# Shot-Clock-Remote.net
KiCad netlist of a schematic drawn in Altium Designer
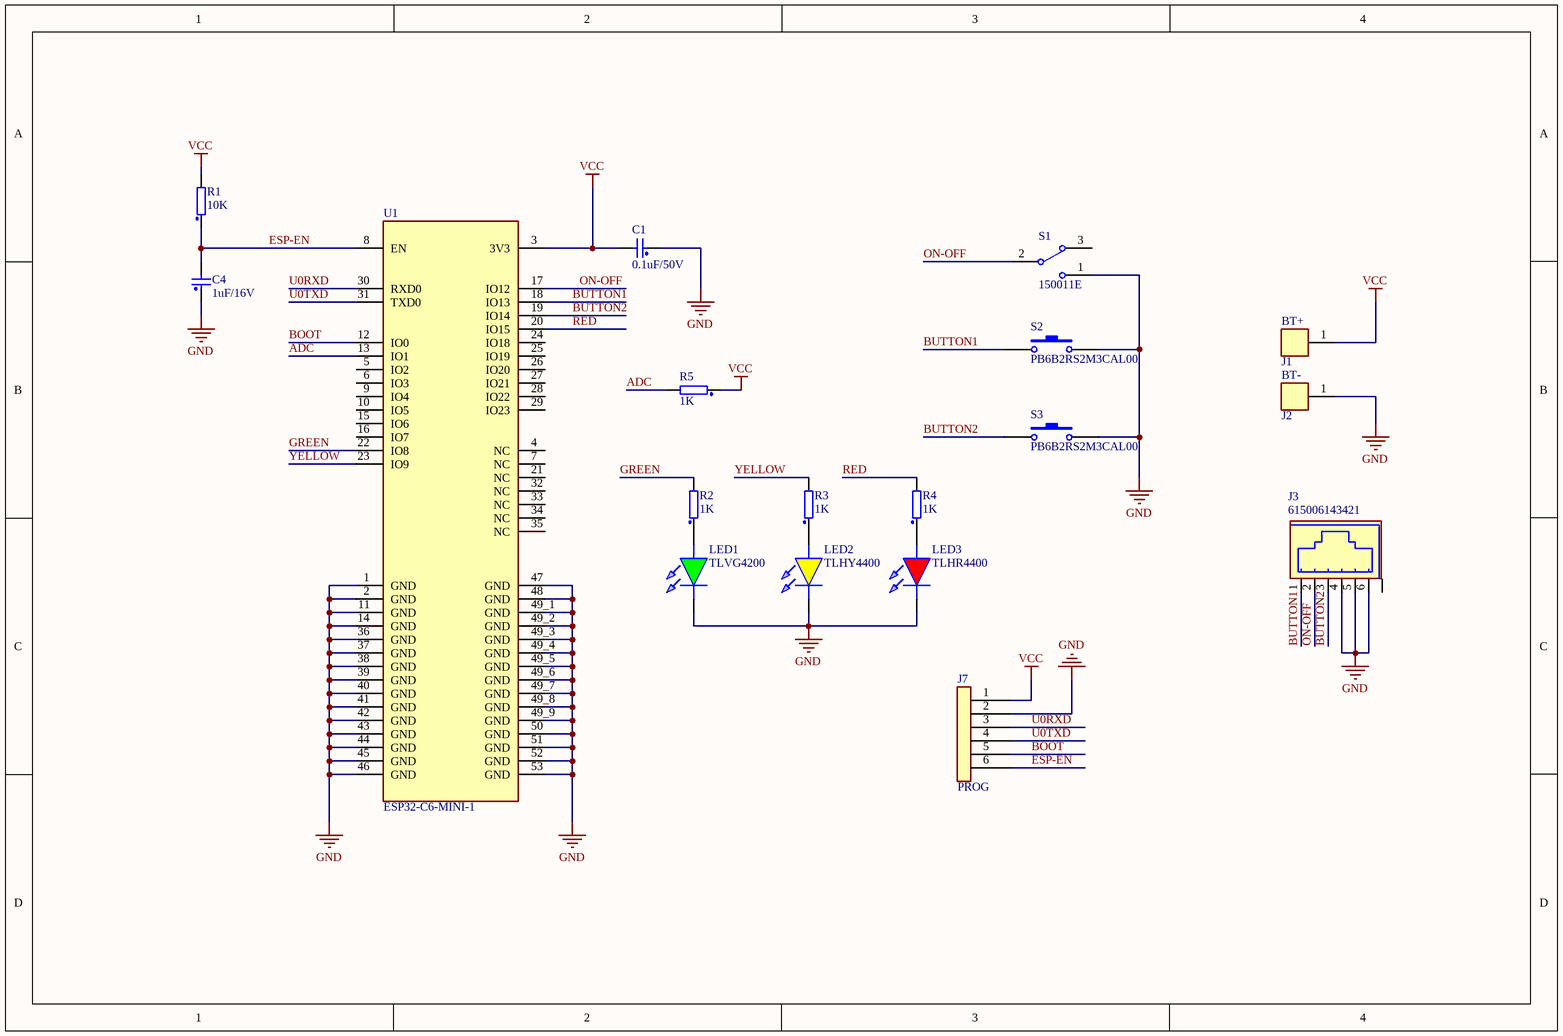
[diagram p0: Shot-Clock-Remote.SchDoc]

(export (version "E")
  (design (tool "Eeschema 10.0.6"))
  (components
    (comp (ref "C1")
      (value "0.1uF/50V")
      (footprint "CAP-0603")
      (description "Multilayer Ceramic Capacitors MLCC - SMD/SMT 50V 100nF X7R 0603 10%")
      (fields
        (field (name "MANUFACTURER") "YAGEO")
        (field (name "MANUFACTURER PART NUMBER") "CS0603KRX7R9BB104")
      )
      (libsource (lib "Dropbox") (part "CAP"))
    )
    (comp (ref "C4")
      (value "1uF/16V")
      (footprint "CAP-0603")
      (description "1 µF ±10% 25V Ceramic Capacitor X5R 0603 (1608 Metric)")
      (fields
        (field (name "MANUFACTURER") "YAGEO")
        (field (name "MANUFACTURER PART NUMBER") "CC0603KRX7R7BB105")
      )
      (libsource (lib "Dropbox") (part "CAP"))
    )
    (comp (ref "J1")
      (value "BT+")
      (footprint "BT_PAD")
      (description "NO FIT")
      (libsource (lib "ESP-Button") (part "BK-82"))
    )
    (comp (ref "J2")
      (value "BT-")
      (footprint "BT_PAD")
      (description "NO FIT")
      (libsource (lib "ESP-Button") (part "BK-82"))
    )
    (comp (ref "J3")
      (value "615006143421")
      (footprint "615006143421")
      (description "Modular Connectors / Ethernet Connectors WR-COM Modular Jack Horztl 1.5A")
      (fields (field (name "MANUFACTURER") "Wurth Elektronik"))
      (libsource (lib "615006143421") (part "615006143421"))
    )
    (comp (ref "J7")
      (value "PROG")
      (footprint "HEADER1X6")
      (description "Connector Header Through Hole 6 position 0.100\" (2.54mm)")
      (fields
        (field (name "MANUFACTURER") "Würth Elektronik")
        (field (name "MANUFACTURER PART NUMBER") "61300611121")
      )
      (libsource (lib "SCJ library") (part "HEADER6_1"))
    )
    (comp (ref "LED1")
      (value "TLVG4200")
      (footprint "LED3MM_GREEN")
      (description "Green 569nm LED Indication - Discrete 2.4V Radial")
      (fields (field (name "MANUFACTURER") "Vishay Semiconductor Opto Division"))
      (libsource (lib "ShotClockRemote") (part "LED GREEN DIP 3mm"))
    )
    (comp (ref "LED2")
      (value "TLHY4400")
      (footprint "LED3MM_YELLOW")
      (description "Yellow 588nm LED Indication - Discrete 2.4V Radial")
      (fields (field (name "MANUFACTURER") "Vishay Semiconductor Opto Division"))
      (libsource (lib "ShotClockRemote") (part "LED YELLOW DIP 3mm"))
    )
    (comp (ref "LED3")
      (value "TLHR4400")
      (footprint "LED3MM_RED")
      (description "Red 619nm LED Indication - Discrete 2V Radial")
      (fields (field (name "MANUFACTURER") "Vishay Semiconductor Opto Division"))
      (libsource (lib "ShotClockRemote") (part "LED RED DIP 3mm"))
    )
    (comp (ref "R1")
      (value "10K")
      (footprint "RES-0603")
      (description "10 kOhms ±1% 0.1W, 1/10W Chip Resistor 0603 (1608 Metric) Moisture Resistant Thick Film")
      (fields
        (field (name "MANUFACTURER PART NUMBER") "RC0603FR-0710KL")
        (field (name "MANUFACTURER") "YAGEO")
      )
      (libsource (lib "ShotClockRemote") (part "RES"))
    )
    (comp (ref "R2")
      (value "1K")
      (footprint "RES-0603")
      (description "1 KOhms ±1% 0.1W, 1/10W Chip Resistor 0603 (1608 Metric) Moisture Resistant Thick Film")
      (fields
        (field (name "MANUFACTURER PART NUMBER") "RC0603FR-071KL")
        (field (name "MANUFACTURER") "YAGEO")
      )
      (libsource (lib "ShotClockRemote") (part "RES1"))
    )
    (comp (ref "R3")
      (value "1K")
      (footprint "RES-0603")
      (description "1 KOhms ±1% 0.1W, 1/10W Chip Resistor 0603 (1608 Metric) Moisture Resistant Thick Film")
      (fields
        (field (name "MANUFACTURER PART NUMBER") "RC0603FR-071KL")
        (field (name "MANUFACTURER") "YAGEO")
      )
      (libsource (lib "ShotClockRemote") (part "RES1"))
    )
    (comp (ref "R4")
      (value "1K")
      (footprint "RES-0603")
      (description "1 KOhms ±1% 0.1W, 1/10W Chip Resistor 0603 (1608 Metric) Moisture Resistant Thick Film")
      (fields
        (field (name "MANUFACTURER PART NUMBER") "RC0603FR-071KL")
        (field (name "MANUFACTURER") "YAGEO")
      )
      (libsource (lib "ShotClockRemote") (part "RES1"))
    )
    (comp (ref "R5")
      (value "1K")
      (footprint "RES-0603")
      (description "1 KOhms ±1% 0.1W, 1/10W Chip Resistor 0603 (1608 Metric) Moisture Resistant Thick Film")
      (fields
        (field (name "MANUFACTURER PART NUMBER") "RC0603FR-071KL")
        (field (name "MANUFACTURER") "YAGEO")
      )
      (libsource (lib "ShotClockRemote") (part "RES1"))
    )
    (comp (ref "S1")
      (value "150011E")
      (footprint "150011E")
      (description "SPDT Subminiature Toggle Switch, Right Angle Mounting, Vertical Actuation")
      (fields (field (name "MANUFACTURER") "EATON"))
      (libsource (lib "Miscellaneous Devices") (part "SW-SPDT"))
    )
    (comp (ref "S2")
      (value "PB6B2RS2M3CAL00")
      (footprint "PB6B2RS2M3CAL00")
      (description "Pushbutton Switch SPST-NO Standard Panel Mount, Front")
      (fields (field (name "MANUFACTURER") "TE Connectivity ALCOSWITCH Switches"))
      (libsource (lib "ShotClockRemote") (part "SW-PB"))
    )
    (comp (ref "S3")
      (value "PB6B2RS2M3CAL00")
      (footprint "PB6B2RS2M3CAL00")
      (description "Pushbutton Switch SPST-NO Standard Panel Mount, Front")
      (fields (field (name "MANUFACTURER") "TE Connectivity ALCOSWITCH Switches"))
      (libsource (lib "ShotClockRemote") (part "SW-PB"))
    )
    (comp (ref "U1")
      (value "ESP32-C6-MINI-1")
      (footprint "XCVR_ESP32-C6-MINI-1")
      (fields
        (field (name "MANUFACTURER PART NUMBER") "ESP32-C3-MINI-1-N4")
        (field (name "MANUFACTURER") "Espressif Systems")
      )
      (libsource (lib "ESP-Button") (part "ESP32-C6-MINI-1"))
    )
  )
  (nets
    (net (code "1") (name "/ADC") (class "Default")
      (node (ref "R5") (pin "2") (pintype "passive"))
      (node (ref "U1") (pin "13") (pinfunction "IO1_13") (pintype "passive"))
    )
    (net (code "2") (name "/BOOT") (class "Default")
      (node (ref "J7") (pin "5") (pintype "passive"))
      (node (ref "U1") (pin "12") (pinfunction "IO0_12") (pintype "passive"))
    )
    (net (code "3") (name "/BUTTON1") (class "Default")
      (node (ref "J3") (pin "1") (pinfunction "6_1") (pintype "passive"))
      (node (ref "S2") (pin "1") (pinfunction "1_1") (pintype "passive"))
      (node (ref "U1") (pin "18") (pinfunction "IO13_18") (pintype "passive"))
    )
    (net (code "4") (name "/BUTTON2") (class "Default")
      (node (ref "J3") (pin "3") (pinfunction "4_3") (pintype "passive"))
      (node (ref "S3") (pin "1") (pinfunction "1_1") (pintype "passive"))
      (node (ref "U1") (pin "19") (pinfunction "IO14_19") (pintype "passive"))
    )
    (net (code "5") (name "/ESP-EN") (class "Default")
      (node (ref "C4") (pin "2") (pinfunction "2_2") (pintype "passive"))
      (node (ref "J7") (pin "6") (pintype "passive"))
      (node (ref "R1") (pin "1") (pintype "passive"))
      (node (ref "U1") (pin "8") (pinfunction "EN_8") (pintype "passive"))
    )
    (net (code "6") (name "/GREEN") (class "Default")
      (node (ref "R2") (pin "2") (pintype "passive"))
      (node (ref "U1") (pin "22") (pinfunction "IO8_22") (pintype "passive"))
    )
    (net (code "7") (name "/ON-OFF") (class "Default")
      (node (ref "J3") (pin "2") (pinfunction "5_2") (pintype "passive"))
      (node (ref "S1") (pin "2") (pinfunction "2_2") (pintype "passive"))
      (node (ref "U1") (pin "17") (pinfunction "IO12_17") (pintype "passive"))
    )
    (net (code "8") (name "/RED") (class "Default")
      (node (ref "R4") (pin "2") (pintype "passive"))
      (node (ref "U1") (pin "20") (pinfunction "IO15_20") (pintype "passive"))
    )
    (net (code "9") (name "/U0RXD") (class "Default")
      (node (ref "J7") (pin "3") (pintype "passive"))
      (node (ref "U1") (pin "30") (pinfunction "RXD0_30") (pintype "passive"))
    )
    (net (code "10") (name "/U0TXD") (class "Default")
      (node (ref "J7") (pin "4") (pintype "passive"))
      (node (ref "U1") (pin "31") (pinfunction "TXD0_31") (pintype "passive"))
    )
    (net (code "11") (name "/YELLOW") (class "Default")
      (node (ref "R3") (pin "2") (pintype "passive"))
      (node (ref "U1") (pin "23") (pinfunction "IO9_23") (pintype "passive"))
    )
    (net (code "12") (name "GND") (class "Default")
      (node (ref "C1") (pin "1") (pinfunction "1_1") (pintype "passive"))
      (node (ref "C4") (pin "1") (pinfunction "1_1") (pintype "passive"))
      (node (ref "J2") (pin "1") (pinfunction "1_1") (pintype "passive"))
      (node (ref "J3") (pin "4") (pinfunction "3_4") (pintype "passive"))
      (node (ref "J3") (pin "5") (pinfunction "2_5") (pintype "passive"))
      (node (ref "J3") (pin "6") (pinfunction "1_6") (pintype "passive"))
      (node (ref "J7") (pin "2") (pintype "passive"))
      (node (ref "LED1") (pin "K") (pinfunction "K_K") (pintype "passive"))
      (node (ref "LED2") (pin "K") (pinfunction "K_K") (pintype "passive"))
      (node (ref "LED3") (pin "K") (pinfunction "K_K") (pintype "passive"))
      (node (ref "S1") (pin "1") (pinfunction "1_1") (pintype "passive"))
      (node (ref "S2") (pin "2") (pinfunction "2_2") (pintype "passive"))
      (node (ref "S3") (pin "2") (pinfunction "2_2") (pintype "passive"))
      (node (ref "U1") (pin "1") (pinfunction "GND_1") (pintype "power_in"))
      (node (ref "U1") (pin "11") (pinfunction "GND_11") (pintype "power_in"))
      (node (ref "U1") (pin "14") (pinfunction "GND_14") (pintype "power_in"))
      (node (ref "U1") (pin "2") (pinfunction "GND_2") (pintype "power_in"))
      (node (ref "U1") (pin "36") (pinfunction "GND_36") (pintype "power_in"))
      (node (ref "U1") (pin "37") (pinfunction "GND_37") (pintype "power_in"))
      (node (ref "U1") (pin "38") (pinfunction "GND_38") (pintype "power_in"))
      (node (ref "U1") (pin "39") (pinfunction "GND_39") (pintype "power_in"))
      (node (ref "U1") (pin "40") (pinfunction "GND_40") (pintype "power_in"))
      (node (ref "U1") (pin "41") (pinfunction "GND_41") (pintype "power_in"))
      (node (ref "U1") (pin "42") (pinfunction "GND_42") (pintype "power_in"))
      (node (ref "U1") (pin "43") (pinfunction "GND_43") (pintype "power_in"))
      (node (ref "U1") (pin "44") (pinfunction "GND_44") (pintype "power_in"))
      (node (ref "U1") (pin "45") (pinfunction "GND_45") (pintype "power_in"))
      (node (ref "U1") (pin "46") (pinfunction "GND_46") (pintype "power_in"))
      (node (ref "U1") (pin "47") (pinfunction "GND_47") (pintype "power_in"))
      (node (ref "U1") (pin "48") (pinfunction "GND_48") (pintype "power_in"))
      (node (ref "U1") (pin "49_1") (pinfunction "GND_49_1") (pintype "power_in"))
      (node (ref "U1") (pin "49_2") (pinfunction "GND_49_2") (pintype "power_in"))
      (node (ref "U1") (pin "49_3") (pinfunction "GND_49_3") (pintype "power_in"))
      (node (ref "U1") (pin "49_4") (pinfunction "GND_49_4") (pintype "power_in"))
      (node (ref "U1") (pin "49_5") (pinfunction "GND_49_5") (pintype "power_in"))
      (node (ref "U1") (pin "49_6") (pinfunction "GND_49_6") (pintype "power_in"))
      (node (ref "U1") (pin "49_7") (pinfunction "GND_49_7") (pintype "power_in"))
      (node (ref "U1") (pin "49_8") (pinfunction "GND_49_8") (pintype "power_in"))
      (node (ref "U1") (pin "49_9") (pinfunction "GND_49_9") (pintype "power_in"))
      (node (ref "U1") (pin "50") (pinfunction "GND_50") (pintype "power_in"))
      (node (ref "U1") (pin "51") (pinfunction "GND_51") (pintype "power_in"))
      (node (ref "U1") (pin "52") (pinfunction "GND_52") (pintype "power_in"))
      (node (ref "U1") (pin "53") (pinfunction "GND_53") (pintype "power_in"))
    )
    (net (code "13") (name "Net-(J3-SHIELD-PadS1)") (class "Default")
      (node (ref "J3") (pin "S1") (pinfunction "SHIELD_S1") (pintype "passive"))
      (node (ref "J3") (pin "S2") (pinfunction "SHIELD_S2") (pintype "passive"))
    )
    (net (code "14") (name "Net-(LED1-PadA)") (class "Default")
      (node (ref "LED1") (pin "A") (pinfunction "A_A") (pintype "passive"))
      (node (ref "R2") (pin "1") (pintype "passive"))
    )
    (net (code "15") (name "Net-(LED2-PadA)") (class "Default")
      (node (ref "LED2") (pin "A") (pinfunction "A_A") (pintype "passive"))
      (node (ref "R3") (pin "1") (pintype "passive"))
    )
    (net (code "16") (name "Net-(LED3-PadA)") (class "Default")
      (node (ref "LED3") (pin "A") (pinfunction "A_A") (pintype "passive"))
      (node (ref "R4") (pin "1") (pintype "passive"))
    )
    (net (code "17") (name "VCC") (class "Default")
      (node (ref "C1") (pin "2") (pinfunction "2_2") (pintype "passive"))
      (node (ref "J1") (pin "1") (pinfunction "1_1") (pintype "passive"))
      (node (ref "J7") (pin "1") (pintype "passive"))
      (node (ref "R1") (pin "2") (pintype "passive"))
      (node (ref "R5") (pin "1") (pintype "passive"))
      (node (ref "U1") (pin "3") (pinfunction "3V3_3") (pintype "power_in"))
    )
    (net (code "18") (name "unconnected-(S1-Pad3)") (class "Default")
      (node (ref "S1") (pin "3") (pinfunction "3_3") (pintype "passive"))
    )
    (net (code "19") (name "unconnected-(U1-IO2-Pad5)") (class "Default")
      (node (ref "U1") (pin "5") (pinfunction "IO2_5") (pintype "passive"))
    )
    (net (code "20") (name "unconnected-(U1-IO3-Pad6)") (class "Default")
      (node (ref "U1") (pin "6") (pinfunction "IO3_6") (pintype "passive"))
    )
    (net (code "21") (name "unconnected-(U1-IO4-Pad9)") (class "Default")
      (node (ref "U1") (pin "9") (pinfunction "IO4_9") (pintype "passive"))
    )
    (net (code "22") (name "unconnected-(U1-IO5-Pad10)") (class "Default")
      (node (ref "U1") (pin "10") (pinfunction "IO5_10") (pintype "passive"))
    )
    (net (code "23") (name "unconnected-(U1-IO6-Pad15)") (class "Default")
      (node (ref "U1") (pin "15") (pinfunction "IO6_15") (pintype "passive"))
    )
    (net (code "24") (name "unconnected-(U1-IO7-Pad16)") (class "Default")
      (node (ref "U1") (pin "16") (pinfunction "IO7_16") (pintype "passive"))
    )
    (net (code "25") (name "unconnected-(U1-IO18-Pad24)") (class "Default")
      (node (ref "U1") (pin "24") (pinfunction "IO18_24") (pintype "passive"))
    )
    (net (code "26") (name "unconnected-(U1-IO19-Pad25)") (class "Default")
      (node (ref "U1") (pin "25") (pinfunction "IO19_25") (pintype "passive"))
    )
    (net (code "27") (name "unconnected-(U1-IO20-Pad26)") (class "Default")
      (node (ref "U1") (pin "26") (pinfunction "IO20_26") (pintype "passive"))
    )
    (net (code "28") (name "unconnected-(U1-IO21-Pad27)") (class "Default")
      (node (ref "U1") (pin "27") (pinfunction "IO21_27") (pintype "passive"))
    )
    (net (code "29") (name "unconnected-(U1-IO22-Pad28)") (class "Default")
      (node (ref "U1") (pin "28") (pinfunction "IO22_28") (pintype "passive"))
    )
    (net (code "30") (name "unconnected-(U1-IO23-Pad29)") (class "Default")
      (node (ref "U1") (pin "29") (pinfunction "IO23_29") (pintype "passive"))
    )
    (net (code "31") (name "unconnected-(U1-NC-Pad4)") (class "Default")
      (node (ref "U1") (pin "4") (pinfunction "NC_4") (pintype "passive"))
    )
    (net (code "32") (name "unconnected-(U1-NC-Pad7)") (class "Default")
      (node (ref "U1") (pin "7") (pinfunction "NC_7") (pintype "passive"))
    )
    (net (code "33") (name "unconnected-(U1-NC-Pad21)") (class "Default")
      (node (ref "U1") (pin "21") (pinfunction "NC_21") (pintype "passive"))
    )
    (net (code "34") (name "unconnected-(U1-NC-Pad32)") (class "Default")
      (node (ref "U1") (pin "32") (pinfunction "NC_32") (pintype "passive"))
    )
    (net (code "35") (name "unconnected-(U1-NC-Pad33)") (class "Default")
      (node (ref "U1") (pin "33") (pinfunction "NC_33") (pintype "passive"))
    )
    (net (code "36") (name "unconnected-(U1-NC-Pad34)") (class "Default")
      (node (ref "U1") (pin "34") (pinfunction "NC_34") (pintype "passive"))
    )
    (net (code "37") (name "unconnected-(U1-NC-Pad35)") (class "Default")
      (node (ref "U1") (pin "35") (pinfunction "NC_35") (pintype "passive"))
    )
  )
)
